# A3000_16MB_Glue.net
KiCad netlist of a schematic drawn in Altium Designer
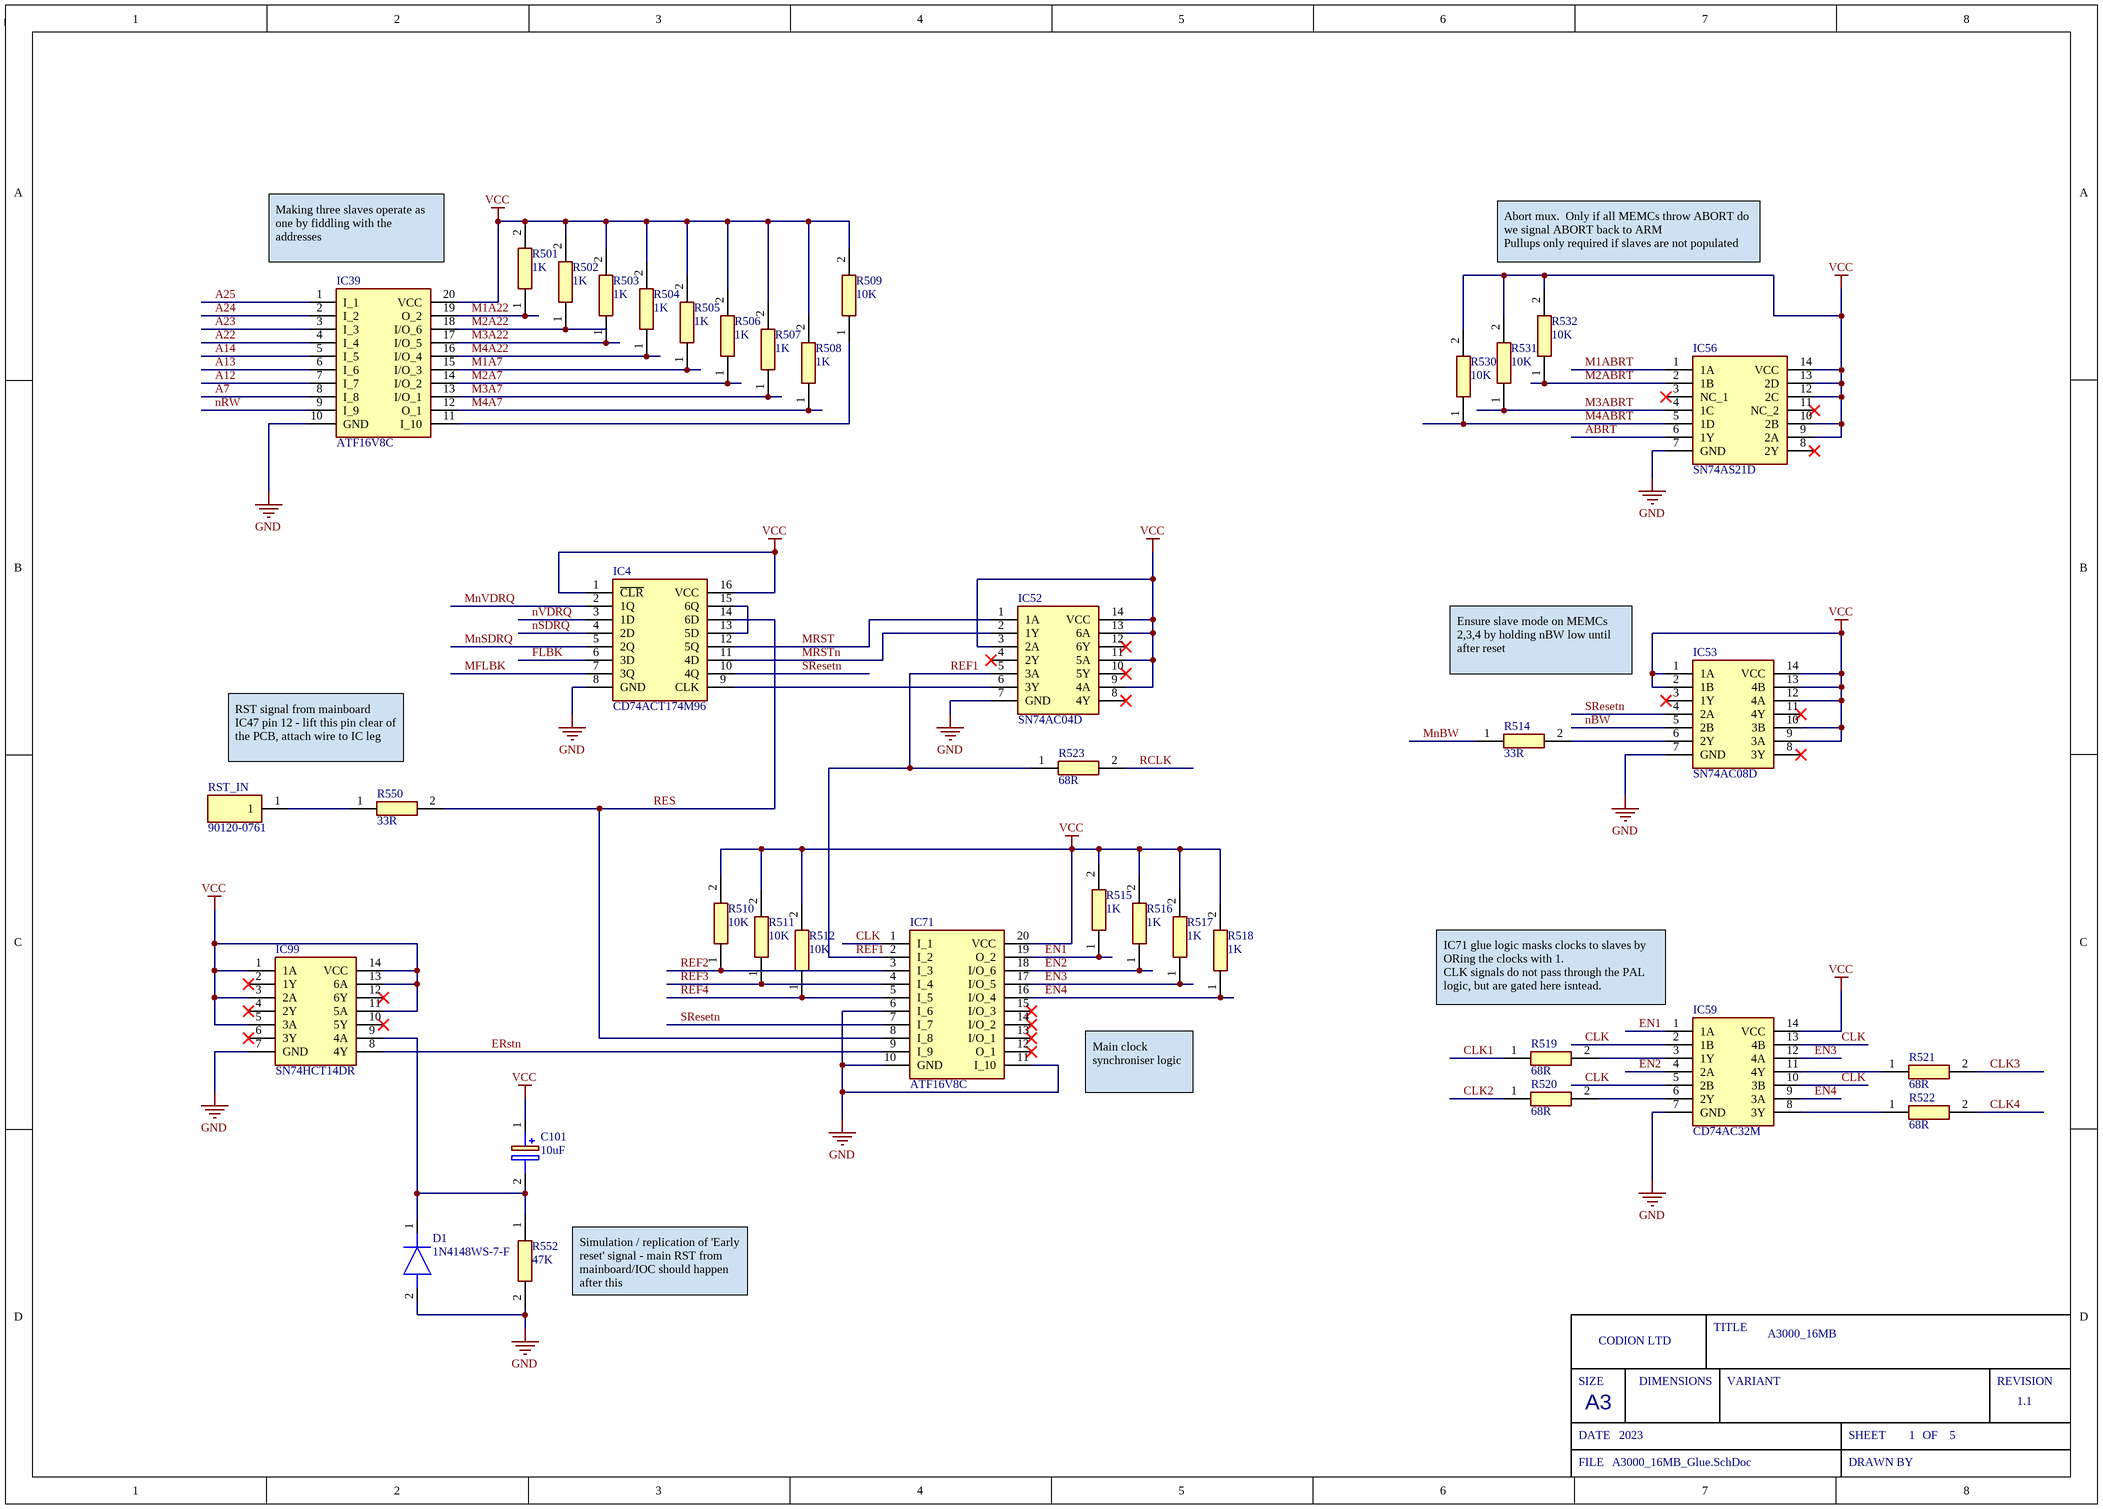
[diagram p0: A3000_16MB_Glue.SchDoc]

(export (version "E")
  (design (tool "Eeschema 10.0.6"))
  (components
    (comp (ref "C101")
      (value "10uF")
      (footprint "SamacSys:EEE0GA101SR")
      (description "Capacitor Polarised")
      (fields
        (field (name "MANUFACTURER_PART_NUMBER") "EEE-1EA100SR")
        (field (name "MOUSER PART NUMBER") "667-EEE-1EA100SR")
      )
      (libsource (lib "*") (part "EEE-1EA100SR"))
    )
    (comp (ref "D1")
      (value "1N4148WS-7-F")
      (footprint "SamacSys:SOD2513X120N")
      (description "Diode")
      (fields (field (name "MOUSER PART NUMBER") "621-1N4148WS-F") (field (name "LCSC PART #") "C2128"))
      (libsource (lib "SamacSys") (part "1N4148WS-7-F"))
    )
    (comp (ref "IC4")
      (value "CD74ACT174M96")
      (footprint "SamacSys:SOIC127P600X175-16N")
      (description "Integrated Circuit")
      (fields (field (name "MOUSER PART NUMBER") "595-CD74ACT174M96"))
      (libsource (lib "*") (part "CD74ACT174M96"))
    )
    (comp (ref "IC39")
      (value "ATF16V8C")
      (footprint "SamacSys:DIP762W66P254L2692H508Q20N")
      (description "Integrated Circuit")
      (fields
        (field (name "MANUFACTURER_PART_NUMBER") "PAL16R4AMJ")
        (field (name "MOUSER PART NUMBER") "595-PAL16R4AMJ")
      )
      (libsource (lib "*") (part "PAL16R4AMJ"))
    )
    (comp (ref "IC52")
      (value "SN74AC04D")
      (footprint "SamacSys:SOIC127P600X175-14N")
      (description "Integrated Circuit")
      (fields (field (name "MOUSER PART NUMBER") "595-SN74AC04D") (field (name "LCSC PART #") "C352940"))
      (libsource (lib "SamacSys") (part "SN74AC04D"))
    )
    (comp (ref "IC53")
      (value "SN74AC08D")
      (footprint "SamacSys:SOIC127P600X175-14N")
      (description "Integrated Circuit")
      (fields (field (name "MOUSER PART NUMBER") "595-SN74AC08D") (field (name "LCSC PART #") "C352941"))
      (libsource (lib "SamacSys") (part "SN74AC08D"))
    )
    (comp (ref "IC56")
      (value "SN74AS21D")
      (footprint "SamacSys:SOIC127P600X175-14N")
      (description "Integrated Circuit")
      (fields (field (name "MOUSER PART NUMBER") "595-SN74AS21D"))
      (libsource (lib "*") (part "SN74AS21D"))
    )
    (comp (ref "IC59")
      (value "CD74AC32M")
      (footprint "SamacSys:SOIC127P600X175-14N")
      (description "Integrated Circuit")
      (fields (field (name "MOUSER PART NUMBER") "595-CD74AC32M") (field (name "LCSC PART #") "C352943"))
      (libsource (lib "SamacSys") (part "CD74AC32M"))
    )
    (comp (ref "IC71")
      (value "ATF16V8C")
      (footprint "SamacSys:DIP762W66P254L2692H508Q20N")
      (description "Integrated Circuit")
      (fields
        (field (name "MANUFACTURER_PART_NUMBER") "PAL16R4AMJ")
        (field (name "MOUSER PART NUMBER") "595-PAL16R4AMJ")
      )
      (libsource (lib "*") (part "PAL16R4AMJ"))
    )
    (comp (ref "IC99")
      (value "SN74HCT14DR")
      (footprint "SamacSys:SOIC127P600X175-14N")
      (description "Integrated Circuit")
      (fields (field (name "MOUSER PART NUMBER") "595-SN74HCT14DR") (field (name "LCSC PART #") "C6769"))
      (libsource (lib "SamacSys") (part "SN74HCT14DR"))
    )
    (comp (ref "R501")
      (value "1K")
      (footprint "SamacSys:RESC1005X40N")
      (description "Resistor")
      (fields
        (field (name "MANUFACTURER_PART_NUMBER") "CRCW04021K00JNED")
        (field (name "MOUSER PART NUMBER") "71-CRCW0402J-1.0K-E3")
      )
      (libsource (lib "SamacSys") (part "CRCW04021K00JNED"))
    )
    (comp (ref "R502")
      (value "1K")
      (footprint "SamacSys:RESC1005X40N")
      (description "Resistor")
      (fields
        (field (name "MANUFACTURER_PART_NUMBER") "CRCW04021K00JNED")
        (field (name "MOUSER PART NUMBER") "71-CRCW0402J-1.0K-E3")
      )
      (libsource (lib "SamacSys") (part "CRCW04021K00JNED"))
    )
    (comp (ref "R503")
      (value "1K")
      (footprint "SamacSys:RESC1005X40N")
      (description "Resistor")
      (fields
        (field (name "MANUFACTURER_PART_NUMBER") "CRCW04021K00JNED")
        (field (name "MOUSER PART NUMBER") "71-CRCW0402J-1.0K-E3")
      )
      (libsource (lib "SamacSys") (part "CRCW04021K00JNED"))
    )
    (comp (ref "R504")
      (value "1K")
      (footprint "SamacSys:RESC1005X40N")
      (description "Resistor")
      (fields
        (field (name "MANUFACTURER_PART_NUMBER") "CRCW04021K00JNED")
        (field (name "MOUSER PART NUMBER") "71-CRCW0402J-1.0K-E3")
      )
      (libsource (lib "SamacSys") (part "CRCW04021K00JNED"))
    )
    (comp (ref "R505")
      (value "1K")
      (footprint "SamacSys:RESC1005X40N")
      (description "Resistor")
      (fields
        (field (name "MANUFACTURER_PART_NUMBER") "CRCW04021K00JNED")
        (field (name "MOUSER PART NUMBER") "71-CRCW0402J-1.0K-E3")
      )
      (libsource (lib "SamacSys") (part "CRCW04021K00JNED"))
    )
    (comp (ref "R506")
      (value "1K")
      (footprint "SamacSys:RESC1005X40N")
      (description "Resistor")
      (fields
        (field (name "MANUFACTURER_PART_NUMBER") "CRCW04021K00JNED")
        (field (name "MOUSER PART NUMBER") "71-CRCW0402J-1.0K-E3")
      )
      (libsource (lib "SamacSys") (part "CRCW04021K00JNED"))
    )
    (comp (ref "R507")
      (value "1K")
      (footprint "SamacSys:RESC1005X40N")
      (description "Resistor")
      (fields
        (field (name "MANUFACTURER_PART_NUMBER") "CRCW04021K00JNED")
        (field (name "MOUSER PART NUMBER") "71-CRCW0402J-1.0K-E3")
      )
      (libsource (lib "SamacSys") (part "CRCW04021K00JNED"))
    )
    (comp (ref "R508")
      (value "1K")
      (footprint "SamacSys:RESC1005X40N")
      (description "Resistor")
      (fields
        (field (name "MANUFACTURER_PART_NUMBER") "CRCW04021K00JNED")
        (field (name "MOUSER PART NUMBER") "71-CRCW0402J-1.0K-E3")
      )
      (libsource (lib "SamacSys") (part "CRCW04021K00JNED"))
    )
    (comp (ref "R509")
      (value "10K")
      (footprint "SamacSys:RESC1005X40N")
      (description "Resistor")
      (fields
        (field (name "MANUFACTURER_PART_NUMBER") "CRCW040210K0FKEDHP")
        (field (name "MOUSER PART NUMBER") "71-CRCW040210K0FKEDH")
      )
      (libsource (lib "SamacSys") (part "CRCW040210K0FKEDHP"))
    )
    (comp (ref "R510")
      (value "10K")
      (footprint "SamacSys:RESC1005X40N")
      (description "Resistor")
      (fields
        (field (name "MANUFACTURER_PART_NUMBER") "CRCW040210K0FKEDHP")
        (field (name "MOUSER PART NUMBER") "71-CRCW040210K0FKEDH")
      )
      (libsource (lib "SamacSys") (part "CRCW040210K0FKEDHP"))
    )
    (comp (ref "R511")
      (value "10K")
      (footprint "SamacSys:RESC1005X40N")
      (description "Resistor")
      (fields
        (field (name "MANUFACTURER_PART_NUMBER") "CRCW040210K0FKEDHP")
        (field (name "MOUSER PART NUMBER") "71-CRCW040210K0FKEDH")
      )
      (libsource (lib "SamacSys") (part "CRCW040210K0FKEDHP"))
    )
    (comp (ref "R512")
      (value "10K")
      (footprint "SamacSys:RESC1005X40N")
      (description "Resistor")
      (fields
        (field (name "MANUFACTURER_PART_NUMBER") "CRCW040210K0FKEDHP")
        (field (name "MOUSER PART NUMBER") "71-CRCW040210K0FKEDH")
      )
      (libsource (lib "SamacSys") (part "CRCW040210K0FKEDHP"))
    )
    (comp (ref "R514")
      (value "33R")
      (footprint "SamacSys:RESC1005X40N")
      (description "Resistor")
      (fields
        (field (name "MANUFACTURER_PART_NUMBER") "CRCW040233R0FKED")
        (field (name "MOUSER PART NUMBER") "71-CRCW0402-33-E3")
      )
      (libsource (lib "SamacSys") (part "CRCW040233R0FKED"))
    )
    (comp (ref "R515")
      (value "1K")
      (footprint "SamacSys:RESC1005X40N")
      (description "Resistor")
      (fields
        (field (name "MANUFACTURER_PART_NUMBER") "CRCW04021K00JNED")
        (field (name "MOUSER PART NUMBER") "71-CRCW0402J-1.0K-E3")
      )
      (libsource (lib "SamacSys") (part "CRCW04021K00JNED"))
    )
    (comp (ref "R516")
      (value "1K")
      (footprint "SamacSys:RESC1005X40N")
      (description "Resistor")
      (fields
        (field (name "MANUFACTURER_PART_NUMBER") "CRCW04021K00JNED")
        (field (name "MOUSER PART NUMBER") "71-CRCW0402J-1.0K-E3")
      )
      (libsource (lib "SamacSys") (part "CRCW04021K00JNED"))
    )
    (comp (ref "R517")
      (value "1K")
      (footprint "SamacSys:RESC1005X40N")
      (description "Resistor")
      (fields
        (field (name "MANUFACTURER_PART_NUMBER") "CRCW04021K00JNED")
        (field (name "MOUSER PART NUMBER") "71-CRCW0402J-1.0K-E3")
      )
      (libsource (lib "SamacSys") (part "CRCW04021K00JNED"))
    )
    (comp (ref "R518")
      (value "1K")
      (footprint "SamacSys:RESC1005X40N")
      (description "Resistor")
      (fields
        (field (name "MANUFACTURER_PART_NUMBER") "CRCW04021K00JNED")
        (field (name "MOUSER PART NUMBER") "71-CRCW0402J-1.0K-E3")
      )
      (libsource (lib "SamacSys") (part "CRCW04021K00JNED"))
    )
    (comp (ref "R519")
      (value "68R")
      (footprint "SamacSys:RESC1005X40N")
      (description "Resistor")
      (fields
        (field (name "MANUFACTURER_PART_NUMBER") "CRCW040268R0FKEDHP")
        (field (name "MOUSER PART NUMBER") "71-CRCW040268R0FKEDH")
      )
      (libsource (lib "SamacSys") (part "CRCW040268R0FKEDHP"))
    )
    (comp (ref "R520")
      (value "68R")
      (footprint "SamacSys:RESC1005X40N")
      (description "Resistor")
      (fields
        (field (name "MANUFACTURER_PART_NUMBER") "CRCW040268R0FKEDHP")
        (field (name "MOUSER PART NUMBER") "71-CRCW040268R0FKEDH")
      )
      (libsource (lib "SamacSys") (part "CRCW040268R0FKEDHP"))
    )
    (comp (ref "R521")
      (value "68R")
      (footprint "SamacSys:RESC1005X40N")
      (description "Resistor")
      (fields
        (field (name "MANUFACTURER_PART_NUMBER") "CRCW040268R0FKEDHP")
        (field (name "MOUSER PART NUMBER") "71-CRCW040268R0FKEDH")
      )
      (libsource (lib "SamacSys") (part "CRCW040268R0FKEDHP"))
    )
    (comp (ref "R522")
      (value "68R")
      (footprint "SamacSys:RESC1005X40N")
      (description "Resistor")
      (fields
        (field (name "MANUFACTURER_PART_NUMBER") "CRCW040268R0FKEDHP")
        (field (name "MOUSER PART NUMBER") "71-CRCW040268R0FKEDH")
      )
      (libsource (lib "SamacSys") (part "CRCW040268R0FKEDHP"))
    )
    (comp (ref "R523")
      (value "68R")
      (footprint "SamacSys:RESC1005X40N")
      (description "Resistor")
      (fields
        (field (name "MANUFACTURER_PART_NUMBER") "CRCW040268R0FKEDHP")
        (field (name "MOUSER PART NUMBER") "71-CRCW040268R0FKEDH")
      )
      (libsource (lib "SamacSys") (part "CRCW040268R0FKEDHP"))
    )
    (comp (ref "R530")
      (value "10K")
      (footprint "SamacSys:RESC1005X40N")
      (description "Resistor")
      (fields
        (field (name "MANUFACTURER_PART_NUMBER") "CRCW040210K0FKEDHP")
        (field (name "MOUSER PART NUMBER") "71-CRCW040210K0FKEDH")
      )
      (libsource (lib "SamacSys") (part "CRCW040210K0FKEDHP"))
    )
    (comp (ref "R531")
      (value "10K")
      (footprint "SamacSys:RESC1005X40N")
      (description "Resistor")
      (fields
        (field (name "MANUFACTURER_PART_NUMBER") "CRCW040210K0FKEDHP")
        (field (name "MOUSER PART NUMBER") "71-CRCW040210K0FKEDH")
      )
      (libsource (lib "SamacSys") (part "CRCW040210K0FKEDHP"))
    )
    (comp (ref "R532")
      (value "10K")
      (footprint "SamacSys:RESC1005X40N")
      (description "Resistor")
      (fields
        (field (name "MANUFACTURER_PART_NUMBER") "CRCW040210K0FKEDHP")
        (field (name "MOUSER PART NUMBER") "71-CRCW040210K0FKEDH")
      )
      (libsource (lib "SamacSys") (part "CRCW040210K0FKEDHP"))
    )
    (comp (ref "R550")
      (value "33R")
      (footprint "SamacSys:RESC1005X40N")
      (description "Resistor")
      (fields
        (field (name "MANUFACTURER_PART_NUMBER") "CRCW040233R0FKED")
        (field (name "MOUSER PART NUMBER") "71-CRCW0402-33-E3")
      )
      (libsource (lib "SamacSys") (part "CRCW040233R0FKED"))
    )
    (comp (ref "R552")
      (value "47K")
      (footprint "SamacSys:RESC1005X40N")
      (description "Resistor")
      (fields
        (field (name "MANUFACTURER_PART_NUMBER") "CRCW040247K0FKED")
        (field (name "MOUSER PART NUMBER") "71-CRCW0402-47K-E3")
      )
      (libsource (lib "SamacSys") (part "CRCW040247K0FKED"))
    )
    (comp (ref "RST_IN")
      (value "90120-0761")
      (footprint "SamacSys:HDRV1W90P0X254_1X1_232X249X560P")
      (description "Connector")
      (fields (field (name "MOUSER PART NUMBER") "538-90120-0761"))
      (libsource (lib "*") (part "90120-0761"))
    )
  )
  (nets
    (net (code "1") (name "/A7") (class "Default")
      (node (ref "IC39") (pin "8") (pinfunction "I_8_8") (pintype "passive"))
    )
    (net (code "2") (name "/A12") (class "Default")
      (node (ref "IC39") (pin "7") (pinfunction "I_7_7") (pintype "passive"))
    )
    (net (code "3") (name "/A13") (class "Default")
      (node (ref "IC39") (pin "6") (pinfunction "I_6_6") (pintype "passive"))
    )
    (net (code "4") (name "/A14") (class "Default")
      (node (ref "IC39") (pin "5") (pinfunction "I_5_5") (pintype "passive"))
    )
    (net (code "5") (name "/A22") (class "Default")
      (node (ref "IC39") (pin "4") (pinfunction "I_4_4") (pintype "passive"))
    )
    (net (code "6") (name "/A23") (class "Default")
      (node (ref "IC39") (pin "3") (pinfunction "I_3_3") (pintype "passive"))
    )
    (net (code "7") (name "/A24") (class "Default")
      (node (ref "IC39") (pin "2") (pinfunction "I_2_2") (pintype "passive"))
    )
    (net (code "8") (name "/A25") (class "Default")
      (node (ref "IC39") (pin "1") (pinfunction "I_1_1") (pintype "passive"))
    )
    (net (code "9") (name "/ABRT") (class "Default")
      (node (ref "IC56") (pin "6") (pinfunction "1Y_6") (pintype "passive"))
    )
    (net (code "10") (name "/CLK") (class "Default")
      (node (ref "IC59") (pin "10") (pinfunction "3B_10") (pintype "passive"))
      (node (ref "IC59") (pin "13") (pinfunction "4B_13") (pintype "passive"))
      (node (ref "IC59") (pin "2") (pinfunction "1B_2") (pintype "passive"))
      (node (ref "IC59") (pin "5") (pinfunction "2B_5") (pintype "passive"))
      (node (ref "IC71") (pin "1") (pinfunction "I_1_1") (pintype "passive"))
    )
    (net (code "11") (name "/CLK1") (class "Default")
      (node (ref "R519") (pin "1") (pinfunction "1_1") (pintype "passive"))
    )
    (net (code "12") (name "/CLK2") (class "Default")
      (node (ref "R520") (pin "1") (pinfunction "1_1") (pintype "passive"))
    )
    (net (code "13") (name "/CLK3") (class "Default")
      (node (ref "R521") (pin "2") (pinfunction "2_2") (pintype "passive"))
    )
    (net (code "14") (name "/CLK4") (class "Default")
      (node (ref "R522") (pin "2") (pinfunction "2_2") (pintype "passive"))
    )
    (net (code "15") (name "/EN1") (class "Default")
      (node (ref "IC59") (pin "1") (pinfunction "1A_1") (pintype "passive"))
      (node (ref "IC71") (pin "19") (pinfunction "O_2_19") (pintype "passive"))
      (node (ref "R515") (pin "1") (pinfunction "1_1") (pintype "passive"))
    )
    (net (code "16") (name "/EN2") (class "Default")
      (node (ref "IC59") (pin "4") (pinfunction "2A_4") (pintype "passive"))
      (node (ref "IC71") (pin "18") (pinfunction "I/O_6_18") (pintype "passive"))
      (node (ref "R516") (pin "1") (pinfunction "1_1") (pintype "passive"))
    )
    (net (code "17") (name "/EN3") (class "Default")
      (node (ref "IC59") (pin "12") (pinfunction "4A_12") (pintype "passive"))
      (node (ref "IC71") (pin "17") (pinfunction "I/O_5_17") (pintype "passive"))
      (node (ref "R517") (pin "1") (pinfunction "1_1") (pintype "passive"))
    )
    (net (code "18") (name "/EN4") (class "Default")
      (node (ref "IC59") (pin "9") (pinfunction "3A_9") (pintype "passive"))
      (node (ref "IC71") (pin "16") (pinfunction "I/O_4_16") (pintype "passive"))
      (node (ref "R518") (pin "1") (pinfunction "1_1") (pintype "passive"))
    )
    (net (code "19") (name "/ERstn") (class "Default")
      (node (ref "IC71") (pin "9") (pinfunction "I_9_9") (pintype "passive"))
      (node (ref "IC99") (pin "8") (pinfunction "4Y_8") (pintype "passive"))
    )
    (net (code "20") (name "/FLBK") (class "Default")
      (node (ref "IC4") (pin "6") (pinfunction "3D_6") (pintype "passive"))
    )
    (net (code "21") (name "/M1A7") (class "Default")
      (node (ref "IC39") (pin "15") (pinfunction "I/O_3_15") (pintype "passive"))
      (node (ref "R505") (pin "1") (pinfunction "1_1") (pintype "passive"))
    )
    (net (code "22") (name "/M1A22") (class "Default")
      (node (ref "IC39") (pin "19") (pinfunction "O_2_19") (pintype "passive"))
      (node (ref "R501") (pin "1") (pinfunction "1_1") (pintype "passive"))
    )
    (net (code "23") (name "/M1ABRT") (class "Default")
      (node (ref "IC56") (pin "1") (pinfunction "1A_1") (pintype "passive"))
    )
    (net (code "24") (name "/M2A7") (class "Default")
      (node (ref "IC39") (pin "14") (pinfunction "I/O_2_14") (pintype "passive"))
      (node (ref "R506") (pin "1") (pinfunction "1_1") (pintype "passive"))
    )
    (net (code "25") (name "/M2A22") (class "Default")
      (node (ref "IC39") (pin "18") (pinfunction "I/O_6_18") (pintype "passive"))
      (node (ref "R502") (pin "1") (pinfunction "1_1") (pintype "passive"))
    )
    (net (code "26") (name "/M2ABRT") (class "Default")
      (node (ref "IC56") (pin "2") (pinfunction "1B_2") (pintype "passive"))
      (node (ref "R532") (pin "1") (pinfunction "1_1") (pintype "passive"))
    )
    (net (code "27") (name "/M3A7") (class "Default")
      (node (ref "IC39") (pin "13") (pinfunction "I/O_1_13") (pintype "passive"))
      (node (ref "R507") (pin "1") (pinfunction "1_1") (pintype "passive"))
    )
    (net (code "28") (name "/M3A22") (class "Default")
      (node (ref "IC39") (pin "17") (pinfunction "I/O_5_17") (pintype "passive"))
      (node (ref "R503") (pin "1") (pinfunction "1_1") (pintype "passive"))
    )
    (net (code "29") (name "/M3ABRT") (class "Default")
      (node (ref "IC56") (pin "4") (pinfunction "1C_4") (pintype "passive"))
      (node (ref "R531") (pin "1") (pinfunction "1_1") (pintype "passive"))
    )
    (net (code "30") (name "/M4A7") (class "Default")
      (node (ref "IC39") (pin "12") (pinfunction "O_1_12") (pintype "passive"))
      (node (ref "R508") (pin "1") (pinfunction "1_1") (pintype "passive"))
    )
    (net (code "31") (name "/M4A22") (class "Default")
      (node (ref "IC39") (pin "16") (pinfunction "I/O_4_16") (pintype "passive"))
      (node (ref "R504") (pin "1") (pinfunction "1_1") (pintype "passive"))
    )
    (net (code "32") (name "/M4ABRT") (class "Default")
      (node (ref "IC56") (pin "5") (pinfunction "1D_5") (pintype "passive"))
      (node (ref "R530") (pin "1") (pinfunction "1_1") (pintype "passive"))
    )
    (net (code "33") (name "/MFLBK") (class "Default")
      (node (ref "IC4") (pin "7") (pinfunction "3Q_7") (pintype "passive"))
    )
    (net (code "34") (name "/MRST") (class "Default")
      (node (ref "IC4") (pin "12") (pinfunction "5Q_12") (pintype "passive"))
      (node (ref "IC52") (pin "1") (pinfunction "1A_1") (pintype "passive"))
    )
    (net (code "35") (name "/MRSTn") (class "Default")
      (node (ref "IC4") (pin "11") (pinfunction "4D_11") (pintype "passive"))
      (node (ref "IC52") (pin "2") (pinfunction "1Y_2") (pintype "passive"))
    )
    (net (code "36") (name "/MnBW") (class "Default")
      (node (ref "R514") (pin "1") (pinfunction "1_1") (pintype "passive"))
    )
    (net (code "37") (name "/MnSDRQ") (class "Default")
      (node (ref "IC4") (pin "5") (pinfunction "2Q_5") (pintype "passive"))
    )
    (net (code "38") (name "/MnVDRQ") (class "Default")
      (node (ref "IC4") (pin "2") (pinfunction "1Q_2") (pintype "passive"))
    )
    (net (code "39") (name "/RCLK") (class "Default")
      (node (ref "R523") (pin "2") (pinfunction "2_2") (pintype "passive"))
    )
    (net (code "40") (name "/REF1") (class "Default")
      (node (ref "IC52") (pin "5") (pinfunction "3A_5") (pintype "passive"))
      (node (ref "IC71") (pin "2") (pinfunction "I_2_2") (pintype "passive"))
      (node (ref "R523") (pin "1") (pinfunction "1_1") (pintype "passive"))
    )
    (net (code "41") (name "/REF2") (class "Default")
      (node (ref "IC71") (pin "3") (pinfunction "I_3_3") (pintype "passive"))
      (node (ref "R510") (pin "1") (pinfunction "1_1") (pintype "passive"))
    )
    (net (code "42") (name "/REF3") (class "Default")
      (node (ref "IC71") (pin "4") (pinfunction "I_4_4") (pintype "passive"))
      (node (ref "R511") (pin "1") (pinfunction "1_1") (pintype "passive"))
    )
    (net (code "43") (name "/REF4") (class "Default")
      (node (ref "IC71") (pin "5") (pinfunction "I_5_5") (pintype "passive"))
      (node (ref "R512") (pin "1") (pinfunction "1_1") (pintype "passive"))
    )
    (net (code "44") (name "/RES") (class "Default")
      (node (ref "IC4") (pin "14") (pinfunction "6D_14") (pintype "passive"))
      (node (ref "IC71") (pin "8") (pinfunction "I_8_8") (pintype "passive"))
      (node (ref "R550") (pin "2") (pinfunction "2_2") (pintype "passive"))
    )
    (net (code "45") (name "/SResetn") (class "Default")
      (node (ref "IC4") (pin "10") (pinfunction "4Q_10") (pintype "passive"))
      (node (ref "IC53") (pin "4") (pinfunction "2A_4") (pintype "passive"))
      (node (ref "IC71") (pin "7") (pinfunction "I_7_7") (pintype "passive"))
    )
    (net (code "46") (name "/nBW") (class "Default")
      (node (ref "IC53") (pin "5") (pinfunction "2B_5") (pintype "passive"))
    )
    (net (code "47") (name "/nRW") (class "Default")
      (node (ref "IC39") (pin "9") (pinfunction "I_9_9") (pintype "passive"))
    )
    (net (code "48") (name "/nSDRQ") (class "Default")
      (node (ref "IC4") (pin "4") (pinfunction "2D_4") (pintype "passive"))
    )
    (net (code "49") (name "/nVDRQ") (class "Default")
      (node (ref "IC4") (pin "3") (pinfunction "1D_3") (pintype "passive"))
    )
    (net (code "50") (name "GND") (class "Default")
      (node (ref "D1") (pin "2") (pinfunction "A_2") (pintype "passive"))
      (node (ref "IC39") (pin "10") (pinfunction "GND_10") (pintype "passive"))
      (node (ref "IC4") (pin "8") (pinfunction "GND_8") (pintype "passive"))
      (node (ref "IC52") (pin "7") (pinfunction "GND_7") (pintype "passive"))
      (node (ref "IC53") (pin "7") (pinfunction "GND_7") (pintype "passive"))
      (node (ref "IC56") (pin "7") (pinfunction "GND_7") (pintype "passive"))
      (node (ref "IC59") (pin "7") (pinfunction "GND_7") (pintype "passive"))
      (node (ref "IC71") (pin "10") (pinfunction "GND_10") (pintype "passive"))
      (node (ref "IC71") (pin "11") (pinfunction "I_10_11") (pintype "passive"))
      (node (ref "IC71") (pin "6") (pinfunction "I_6_6") (pintype "passive"))
      (node (ref "IC99") (pin "7") (pinfunction "GND_7") (pintype "passive"))
      (node (ref "R552") (pin "2") (pinfunction "2_2") (pintype "passive"))
    )
    (net (code "51") (name "Net-(C101--)") (class "Default")
      (node (ref "C101") (pin "2") (pinfunction "-_2") (pintype "passive"))
      (node (ref "D1") (pin "1") (pinfunction "K_1") (pintype "passive"))
      (node (ref "IC99") (pin "9") (pinfunction "4A_9") (pintype "passive"))
      (node (ref "R552") (pin "1") (pinfunction "1_1") (pintype "passive"))
    )
    (net (code "52") (name "Net-(IC4-5D)") (class "Default")
      (node (ref "IC4") (pin "13") (pinfunction "5D_13") (pintype "passive"))
      (node (ref "IC4") (pin "15") (pinfunction "6Q_15") (pintype "passive"))
    )
    (net (code "53") (name "Net-(IC4-CLK)") (class "Default")
      (node (ref "IC4") (pin "9") (pinfunction "CLK_9") (pintype "passive"))
      (node (ref "IC52") (pin "6") (pinfunction "3Y_6") (pintype "passive"))
    )
    (net (code "54") (name "Net-(IC39-I_10)") (class "Default")
      (node (ref "IC39") (pin "11") (pinfunction "I_10_11") (pintype "passive"))
      (node (ref "R509") (pin "1") (pinfunction "1_1") (pintype "passive"))
    )
    (net (code "55") (name "Net-(IC53-2Y)") (class "Default")
      (node (ref "IC53") (pin "6") (pinfunction "2Y_6") (pintype "passive"))
      (node (ref "R514") (pin "2") (pinfunction "2_2") (pintype "passive"))
    )
    (net (code "56") (name "Net-(IC59-1Y)") (class "Default")
      (node (ref "IC59") (pin "3") (pinfunction "1Y_3") (pintype "passive"))
      (node (ref "R519") (pin "2") (pinfunction "2_2") (pintype "passive"))
    )
    (net (code "57") (name "Net-(IC59-2Y)") (class "Default")
      (node (ref "IC59") (pin "6") (pinfunction "2Y_6") (pintype "passive"))
      (node (ref "R520") (pin "2") (pinfunction "2_2") (pintype "passive"))
    )
    (net (code "58") (name "Net-(IC59-3Y)") (class "Default")
      (node (ref "IC59") (pin "8") (pinfunction "3Y_8") (pintype "passive"))
      (node (ref "R522") (pin "1") (pinfunction "1_1") (pintype "passive"))
    )
    (net (code "59") (name "Net-(IC59-4Y)") (class "Default")
      (node (ref "IC59") (pin "11") (pinfunction "4Y_11") (pintype "passive"))
      (node (ref "R521") (pin "1") (pinfunction "1_1") (pintype "passive"))
    )
    (net (code "60") (name "Net-(R550-Pad1)") (class "Default")
      (node (ref "R550") (pin "1") (pinfunction "1_1") (pintype "passive"))
      (node (ref "RST_IN") (pin "1") (pinfunction "1_1") (pintype "passive"))
    )
    (net (code "61") (name "VCC") (class "Default")
      (node (ref "C101") (pin "1") (pinfunction "+_1") (pintype "passive"))
      (node (ref "IC39") (pin "20") (pinfunction "VCC_20") (pintype "passive"))
      (node (ref "IC4") (pin "1") (pinfunction "~{CLR}_1") (pintype "passive"))
      (node (ref "IC4") (pin "16") (pinfunction "VCC_16") (pintype "passive"))
      (node (ref "IC52") (pin "11") (pinfunction "5A_11") (pintype "passive"))
      (node (ref "IC52") (pin "13") (pinfunction "6A_13") (pintype "passive"))
      (node (ref "IC52") (pin "14") (pinfunction "VCC_14") (pintype "passive"))
      (node (ref "IC52") (pin "3") (pinfunction "2A_3") (pintype "passive"))
      (node (ref "IC52") (pin "9") (pinfunction "4A_9") (pintype "passive"))
      (node (ref "IC53") (pin "1") (pinfunction "1A_1") (pintype "passive"))
      (node (ref "IC53") (pin "10") (pinfunction "3B_10") (pintype "passive"))
      (node (ref "IC53") (pin "12") (pinfunction "4A_12") (pintype "passive"))
      (node (ref "IC53") (pin "13") (pinfunction "4B_13") (pintype "passive"))
      (node (ref "IC53") (pin "14") (pinfunction "VCC_14") (pintype "passive"))
      (node (ref "IC53") (pin "2") (pinfunction "1B_2") (pintype "passive"))
      (node (ref "IC53") (pin "9") (pinfunction "3A_9") (pintype "passive"))
      (node (ref "IC56") (pin "10") (pinfunction "2B_10") (pintype "passive"))
      (node (ref "IC56") (pin "12") (pinfunction "2C_12") (pintype "passive"))
      (node (ref "IC56") (pin "13") (pinfunction "2D_13") (pintype "passive"))
      (node (ref "IC56") (pin "14") (pinfunction "VCC_14") (pintype "passive"))
      (node (ref "IC56") (pin "9") (pinfunction "2A_9") (pintype "passive"))
      (node (ref "IC59") (pin "14") (pinfunction "VCC_14") (pintype "passive"))
      (node (ref "IC71") (pin "20") (pinfunction "VCC_20") (pintype "passive"))
      (node (ref "IC99") (pin "1") (pinfunction "1A_1") (pintype "passive"))
      (node (ref "IC99") (pin "11") (pinfunction "5A_11") (pintype "passive"))
      (node (ref "IC99") (pin "13") (pinfunction "6A_13") (pintype "passive"))
      (node (ref "IC99") (pin "14") (pinfunction "VCC_14") (pintype "passive"))
      (node (ref "IC99") (pin "3") (pinfunction "2A_3") (pintype "passive"))
      (node (ref "IC99") (pin "5") (pinfunction "3A_5") (pintype "passive"))
      (node (ref "R501") (pin "2") (pinfunction "2_2") (pintype "passive"))
      (node (ref "R502") (pin "2") (pinfunction "2_2") (pintype "passive"))
      (node (ref "R503") (pin "2") (pinfunction "2_2") (pintype "passive"))
      (node (ref "R504") (pin "2") (pinfunction "2_2") (pintype "passive"))
      (node (ref "R505") (pin "2") (pinfunction "2_2") (pintype "passive"))
      (node (ref "R506") (pin "2") (pinfunction "2_2") (pintype "passive"))
      (node (ref "R507") (pin "2") (pinfunction "2_2") (pintype "passive"))
      (node (ref "R508") (pin "2") (pinfunction "2_2") (pintype "passive"))
      (node (ref "R509") (pin "2") (pinfunction "2_2") (pintype "passive"))
      (node (ref "R510") (pin "2") (pinfunction "2_2") (pintype "passive"))
      (node (ref "R511") (pin "2") (pinfunction "2_2") (pintype "passive"))
      (node (ref "R512") (pin "2") (pinfunction "2_2") (pintype "passive"))
      (node (ref "R515") (pin "2") (pinfunction "2_2") (pintype "passive"))
      (node (ref "R516") (pin "2") (pinfunction "2_2") (pintype "passive"))
      (node (ref "R517") (pin "2") (pinfunction "2_2") (pintype "passive"))
      (node (ref "R518") (pin "2") (pinfunction "2_2") (pintype "passive"))
      (node (ref "R530") (pin "2") (pinfunction "2_2") (pintype "passive"))
      (node (ref "R531") (pin "2") (pinfunction "2_2") (pintype "passive"))
      (node (ref "R532") (pin "2") (pinfunction "2_2") (pintype "passive"))
    )
    (net (code "62") (name "unconnected-(IC52-2Y-Pad4)") (class "Default")
      (node (ref "IC52") (pin "4") (pinfunction "2Y_4") (pintype "passive+no_connect"))
    )
    (net (code "63") (name "unconnected-(IC52-4Y-Pad8)") (class "Default")
      (node (ref "IC52") (pin "8") (pinfunction "4Y_8") (pintype "passive+no_connect"))
    )
    (net (code "64") (name "unconnected-(IC52-5Y-Pad10)") (class "Default")
      (node (ref "IC52") (pin "10") (pinfunction "5Y_10") (pintype "passive+no_connect"))
    )
    (net (code "65") (name "unconnected-(IC52-6Y-Pad12)") (class "Default")
      (node (ref "IC52") (pin "12") (pinfunction "6Y_12") (pintype "passive+no_connect"))
    )
    (net (code "66") (name "unconnected-(IC53-1Y-Pad3)") (class "Default")
      (node (ref "IC53") (pin "3") (pinfunction "1Y_3") (pintype "passive+no_connect"))
    )
    (net (code "67") (name "unconnected-(IC53-3Y-Pad8)") (class "Default")
      (node (ref "IC53") (pin "8") (pinfunction "3Y_8") (pintype "passive+no_connect"))
    )
    (net (code "68") (name "unconnected-(IC53-4Y-Pad11)") (class "Default")
      (node (ref "IC53") (pin "11") (pinfunction "4Y_11") (pintype "passive+no_connect"))
    )
    (net (code "69") (name "unconnected-(IC56-2Y-Pad8)") (class "Default")
      (node (ref "IC56") (pin "8") (pinfunction "2Y_8") (pintype "passive+no_connect"))
    )
    (net (code "70") (name "unconnected-(IC56-NC_1-Pad3)") (class "Default")
      (node (ref "IC56") (pin "3") (pinfunction "NC_1_3") (pintype "passive+no_connect"))
    )
    (net (code "71") (name "unconnected-(IC56-NC_2-Pad11)") (class "Default")
      (node (ref "IC56") (pin "11") (pinfunction "NC_2_11") (pintype "passive+no_connect"))
    )
    (net (code "72") (name "unconnected-(IC71-I{slash}O_1-Pad13)") (class "Default")
      (node (ref "IC71") (pin "13") (pinfunction "I/O_1_13") (pintype "passive+no_connect"))
    )
    (net (code "73") (name "unconnected-(IC71-I{slash}O_2-Pad14)") (class "Default")
      (node (ref "IC71") (pin "14") (pinfunction "I/O_2_14") (pintype "passive+no_connect"))
    )
    (net (code "74") (name "unconnected-(IC71-I{slash}O_3-Pad15)") (class "Default")
      (node (ref "IC71") (pin "15") (pinfunction "I/O_3_15") (pintype "passive+no_connect"))
    )
    (net (code "75") (name "unconnected-(IC71-O_1-Pad12)") (class "Default")
      (node (ref "IC71") (pin "12") (pinfunction "O_1_12") (pintype "passive+no_connect"))
    )
    (net (code "76") (name "unconnected-(IC99-1Y-Pad2)") (class "Default")
      (node (ref "IC99") (pin "2") (pinfunction "1Y_2") (pintype "passive+no_connect"))
    )
    (net (code "77") (name "unconnected-(IC99-2Y-Pad4)") (class "Default")
      (node (ref "IC99") (pin "4") (pinfunction "2Y_4") (pintype "passive+no_connect"))
    )
    (net (code "78") (name "unconnected-(IC99-3Y-Pad6)") (class "Default")
      (node (ref "IC99") (pin "6") (pinfunction "3Y_6") (pintype "passive+no_connect"))
    )
    (net (code "79") (name "unconnected-(IC99-5Y-Pad10)") (class "Default")
      (node (ref "IC99") (pin "10") (pinfunction "5Y_10") (pintype "passive+no_connect"))
    )
    (net (code "80") (name "unconnected-(IC99-6Y-Pad12)") (class "Default")
      (node (ref "IC99") (pin "12") (pinfunction "6Y_12") (pintype "passive+no_connect"))
    )
  )
)
